# attiny85_LED.net
KiCad netlist of a schematic drawn in EAGLE
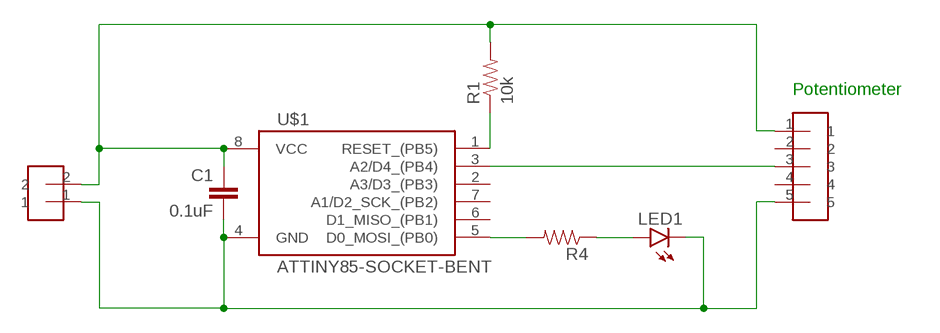
[diagram p0: schematic, sheet 1]

(export (version "E")
  (design (tool "Eeschema 10.0.6"))
  (components
    (comp (ref "C1")
      (value "0.1uF")
      (footprint "eagle-import:0805")
      (libsource (lib "eagle-import") (part "CAP-0805"))
    )
    (comp (ref "LED1")
      (value "LED0603")
      (footprint "eagle-import:LED-0603")
      (libsource (lib "eagle-import") (part "LED0603"))
    )
    (comp (ref "POTENTIOMETER")
      (value "HEADER-5")
      (footprint "eagle-import:HEADER-5")
      (libsource (lib "eagle-import") (part "HEADER-5"))
    )
    (comp (ref "R1")
      (value "10k")
      (footprint "eagle-import:0805")
      (libsource (lib "eagle-import") (part "RESISTOR-0805"))
    )
    (comp (ref "R4")
      (value "RESISTOR0603")
      (footprint "eagle-import:0603-RES")
      (libsource (lib "eagle-import") (part "RESISTOR0603"))
    )
    (comp (ref "U$1")
      (value "ATTINY85-SOCKET-BENT")
      (footprint "eagle-import:SOCKET-8PIN-BENT")
      (libsource (lib "eagle-import") (part "ATTINY85-SOCKET-BENT"))
    )
    (comp (ref "U$3")
      (value "HEADER-2")
      (footprint "eagle-import:HEADER-2")
      (libsource (lib "eagle-import") (part "HEADER-2"))
    )
  )
  (nets
    (net (code "1") (name "Net-(LED1-PadA)") (class "Default")
      (node (ref "LED1") (pin "A") (pinfunction "A_A") (pintype "passive"))
      (node (ref "R4") (pin "1") (pinfunction "1_1") (pintype "passive"))
    )
    (net (code "2") (name "Net-(U$1-A2{slash}D4_(PB4))") (class "Default")
      (node (ref "POTENTIOMETER") (pin "3") (pinfunction "3_3") (pintype "bidirectional"))
      (node (ref "U$1") (pin "3") (pinfunction "A2/D4_(PB4)_3") (pintype "bidirectional"))
    )
    (net (code "3") (name "Net-(U$1-D0_MOSI_(PB0))") (class "Default")
      (node (ref "R4") (pin "2") (pinfunction "2_2") (pintype "passive"))
      (node (ref "U$1") (pin "5") (pinfunction "D0_MOSI_(PB0)_5") (pintype "bidirectional"))
    )
    (net (code "4") (name "Net-(U$1-GND)") (class "Default")
      (node (ref "C1") (pin "2") (pinfunction "2_2") (pintype "passive"))
      (node (ref "LED1") (pin "C") (pinfunction "C_C") (pintype "passive"))
      (node (ref "POTENTIOMETER") (pin "5") (pinfunction "5_5") (pintype "bidirectional"))
      (node (ref "U$1") (pin "4") (pinfunction "GND_4") (pintype "power_in"))
      (node (ref "U$3") (pin "1") (pinfunction "1_1") (pintype "bidirectional"))
    )
    (net (code "5") (name "Net-(U$1-RESET_(PB5))") (class "Default")
      (node (ref "R1") (pin "1") (pinfunction "1_1") (pintype "passive"))
      (node (ref "U$1") (pin "1") (pinfunction "RESET_(PB5)_1") (pintype "bidirectional"))
    )
    (net (code "6") (name "Net-(U$1-VCC)") (class "Default")
      (node (ref "C1") (pin "1") (pinfunction "1_1") (pintype "passive"))
      (node (ref "POTENTIOMETER") (pin "1") (pinfunction "1_1") (pintype "bidirectional"))
      (node (ref "R1") (pin "2") (pinfunction "2_2") (pintype "passive"))
      (node (ref "U$1") (pin "8") (pinfunction "VCC_8") (pintype "power_in"))
      (node (ref "U$3") (pin "2") (pinfunction "2_2") (pintype "bidirectional"))
    )
    (net (code "7") (name "unconnected-(POTENTIOMETER-Pad2)") (class "Default")
      (node (ref "POTENTIOMETER") (pin "2") (pinfunction "2_2") (pintype "bidirectional"))
    )
    (net (code "8") (name "unconnected-(POTENTIOMETER-Pad4)") (class "Default")
      (node (ref "POTENTIOMETER") (pin "4") (pinfunction "4_4") (pintype "bidirectional"))
    )
    (net (code "9") (name "unconnected-(U$1-A1{slash}D2_SCK_(PB2)-Pad7)") (class "Default")
      (node (ref "U$1") (pin "7") (pinfunction "A1/D2_SCK_(PB2)_7") (pintype "bidirectional"))
    )
    (net (code "10") (name "unconnected-(U$1-A3{slash}D3_(PB3)-Pad2)") (class "Default")
      (node (ref "U$1") (pin "2") (pinfunction "A3/D3_(PB3)_2") (pintype "bidirectional"))
    )
    (net (code "11") (name "unconnected-(U$1-D1_MISO_(PB1)-Pad6)") (class "Default")
      (node (ref "U$1") (pin "6") (pinfunction "D1_MISO_(PB1)_6") (pintype "bidirectional"))
    )
  )
)
